# platform_smd2_o2.net
KiCad netlist of a schematic drawn in EAGLE
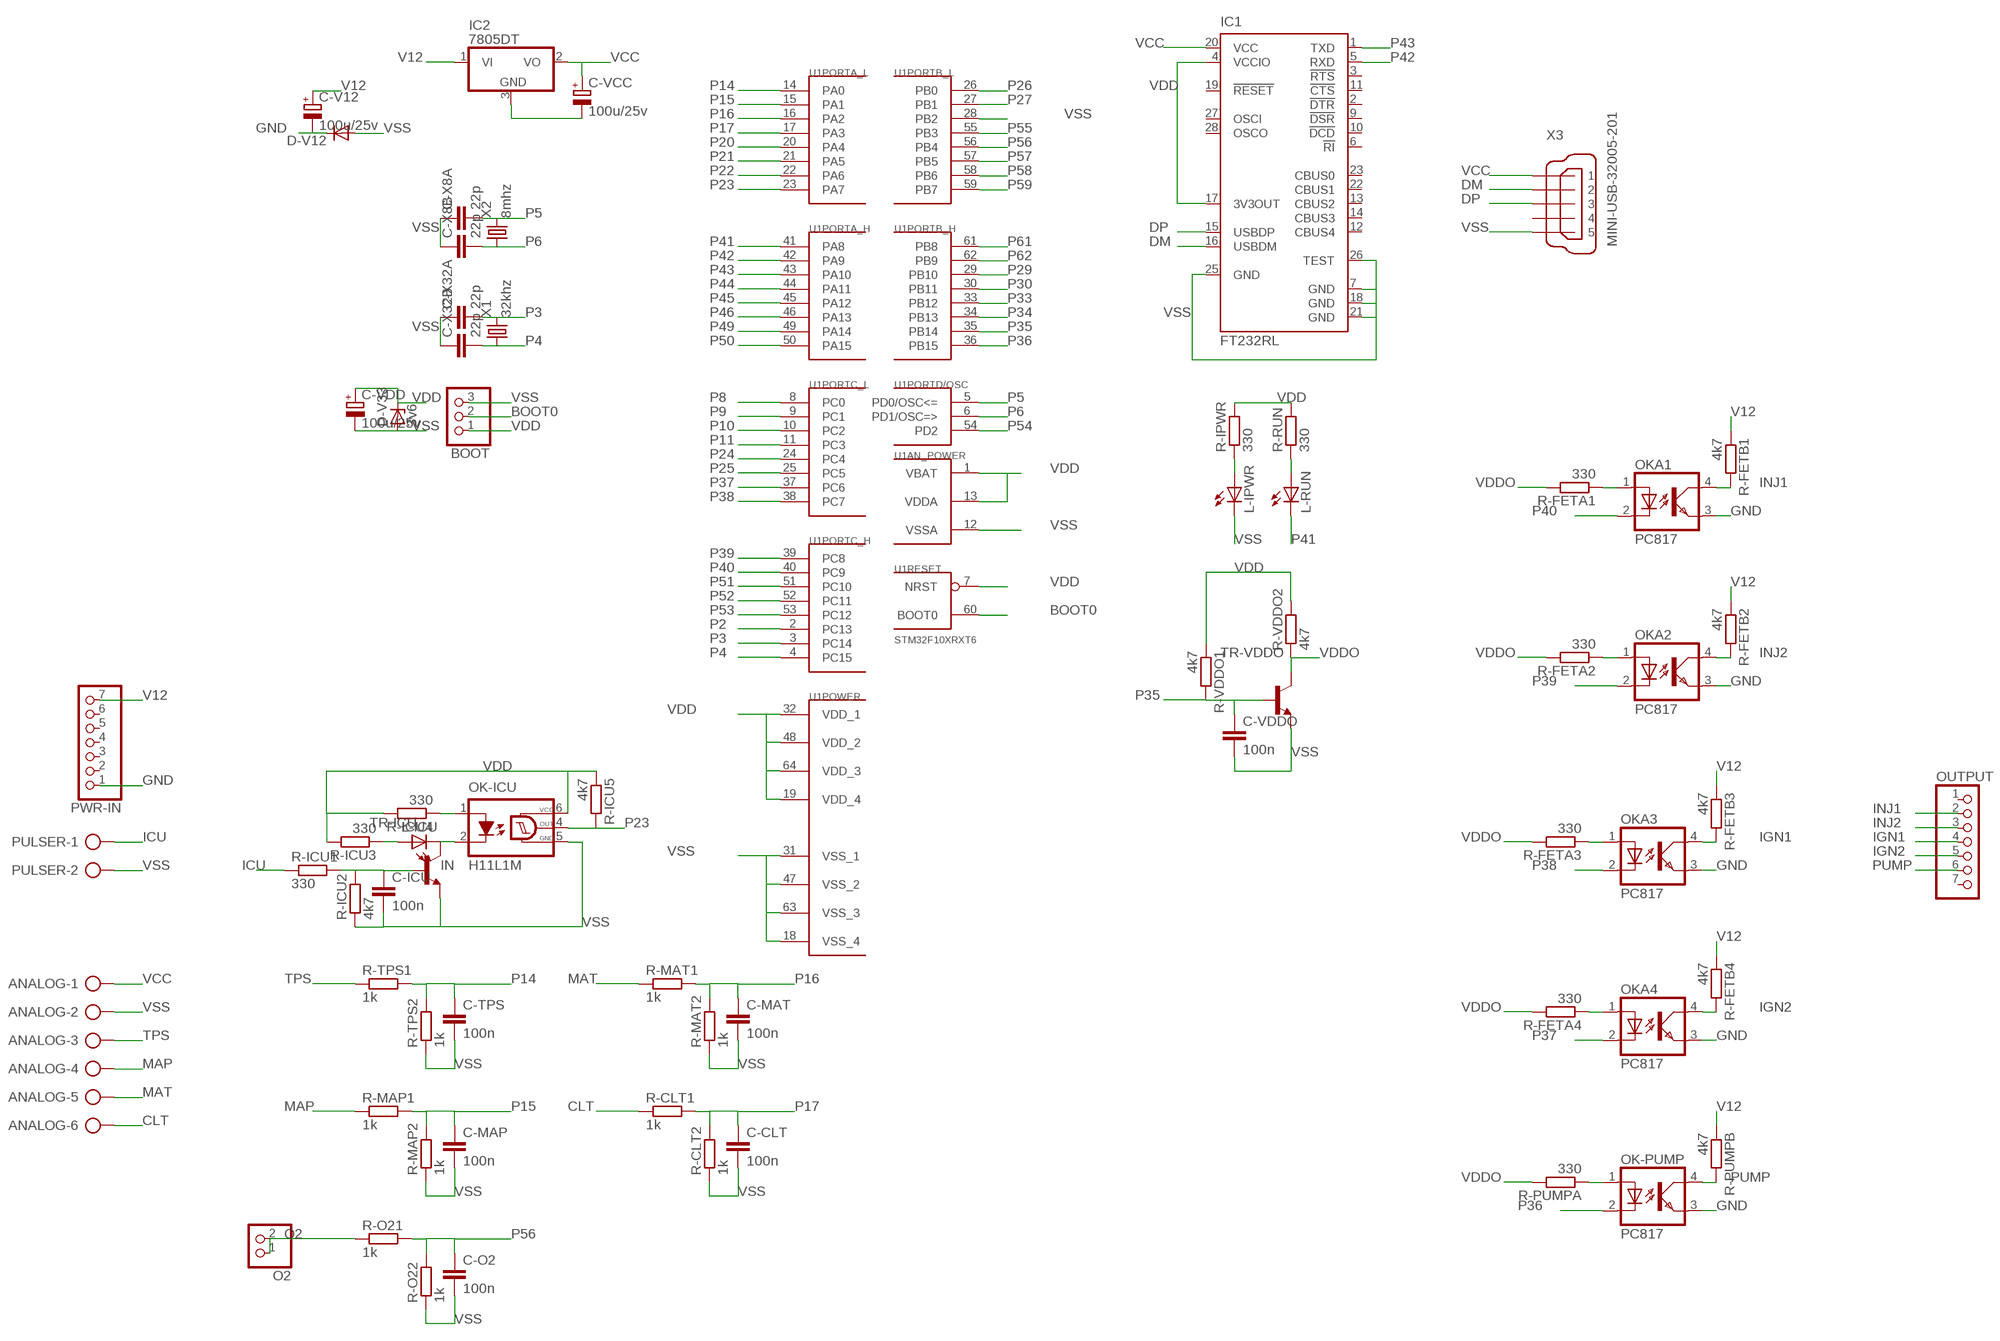
[diagram p0: schematic, sheet 1]

(export (version "E")
  (design (tool "Eeschema 10.0.6"))
  (components
    (comp (ref "ANALOG")
      (value "AK300/6")
      (footprint "eagle-import:AK300_6")
      (libsource (lib "eagle-import") (part "AK300/6"))
    )
    (comp (ref "BOOT")
      (value "PINHD-1X3")
      (footprint "eagle-import:1X03")
      (libsource (lib "eagle-import") (part "PINHD-1X3"))
    )
    (comp (ref "C-CLT")
      (value "100n")
      (footprint "eagle-import:C1206")
      (libsource (lib "eagle-import") (part "C-EUC1206"))
    )
    (comp (ref "C-ICU")
      (value "100n")
      (footprint "eagle-import:C1206")
      (libsource (lib "eagle-import") (part "C-EUC1206"))
    )
    (comp (ref "C-MAP")
      (value "100n")
      (footprint "eagle-import:C1206")
      (libsource (lib "eagle-import") (part "C-EUC1206"))
    )
    (comp (ref "C-MAT")
      (value "100n")
      (footprint "eagle-import:C1206")
      (libsource (lib "eagle-import") (part "C-EUC1206"))
    )
    (comp (ref "C-O2")
      (value "100n")
      (footprint "eagle-import:C1206")
      (libsource (lib "eagle-import") (part "C-EUC1206"))
    )
    (comp (ref "C-TPS")
      (value "100n")
      (footprint "eagle-import:C1206")
      (libsource (lib "eagle-import") (part "C-EUC1206"))
    )
    (comp (ref "C-V12")
      (value "100u/25v")
      (footprint "eagle-import:PANASONIC_D")
      (libsource (lib "eagle-import") (part "CPOL-EUD"))
    )
    (comp (ref "C-VCC")
      (value "100u/25v")
      (footprint "eagle-import:PANASONIC_D")
      (libsource (lib "eagle-import") (part "CPOL-EUD"))
    )
    (comp (ref "C-VDD")
      (value "100u/25v")
      (footprint "eagle-import:PANASONIC_D")
      (libsource (lib "eagle-import") (part "CPOL-EUD"))
    )
    (comp (ref "C-VDDO")
      (value "100n")
      (footprint "eagle-import:C1206")
      (libsource (lib "eagle-import") (part "C-EUC1206"))
    )
    (comp (ref "C-X8A")
      (value "22p")
      (footprint "eagle-import:C1206")
      (libsource (lib "eagle-import") (part "C-EUC1206"))
    )
    (comp (ref "C-X8B")
      (value "22p")
      (footprint "eagle-import:C1206")
      (libsource (lib "eagle-import") (part "C-EUC1206"))
    )
    (comp (ref "C-X32A")
      (value "22p")
      (footprint "eagle-import:C1206")
      (libsource (lib "eagle-import") (part "C-EUC1206"))
    )
    (comp (ref "C-X32B")
      (value "22p")
      (footprint "eagle-import:C1206")
      (libsource (lib "eagle-import") (part "C-EUC1206"))
    )
    (comp (ref "D-V12")
      (value "DIODE-SMB")
      (footprint "eagle-import:SMB")
      (libsource (lib "eagle-import") (part "DIODE-SMB"))
    )
    (comp (ref "D-V33")
      (value "3v6")
      (footprint "eagle-import:SMB")
      (libsource (lib "eagle-import") (part "ZENER-DIODESMB"))
    )
    (comp (ref "IC1")
      (value "FT232RL")
      (footprint "eagle-import:SSOP28")
      (libsource (lib "eagle-import") (part "FT232RL"))
    )
    (comp (ref "IC2")
      (value "7805DT")
      (footprint "eagle-import:TO252")
      (libsource (lib "eagle-import") (part "78DT05"))
    )
    (comp (ref "L-ICU")
      (value "LEDSMT1206")
      (footprint "eagle-import:1206")
      (libsource (lib "eagle-import") (part "LEDSMT1206"))
    )
    (comp (ref "L-IPWR")
      (value "LEDSMT1206")
      (footprint "eagle-import:1206")
      (libsource (lib "eagle-import") (part "LEDSMT1206"))
    )
    (comp (ref "L-RUN")
      (value "LEDSMT1206")
      (footprint "eagle-import:1206")
      (libsource (lib "eagle-import") (part "LEDSMT1206"))
    )
    (comp (ref "O2")
      (value "PINHD-1X2")
      (footprint "eagle-import:1X02")
      (libsource (lib "eagle-import") (part "PINHD-1X2"))
    )
    (comp (ref "OK-ICU")
      (value "H11L1M")
      (footprint "eagle-import:DIL06")
      (fields (field (name "MF") "FAIRCHILD SEMICONDUCTOR") (field (name "MPN") "H11L1-M"))
      (libsource (lib "eagle-import") (part "H11LM1"))
    )
    (comp (ref "OK-PUMP")
      (value "PC817")
      (footprint "eagle-import:DIL04")
      (fields (field (name "MPN") "PC817X4J000F"))
      (libsource (lib "eagle-import") (part "PC817"))
    )
    (comp (ref "OKA1")
      (value "PC817")
      (footprint "eagle-import:DIL04")
      (fields (field (name "MPN") "PC817X4J000F"))
      (libsource (lib "eagle-import") (part "PC817"))
    )
    (comp (ref "OKA2")
      (value "PC817")
      (footprint "eagle-import:DIL04")
      (fields (field (name "MPN") "PC817X4J000F"))
      (libsource (lib "eagle-import") (part "PC817"))
    )
    (comp (ref "OKA3")
      (value "PC817")
      (footprint "eagle-import:DIL04")
      (fields (field (name "MPN") "PC817X4J000F"))
      (libsource (lib "eagle-import") (part "PC817"))
    )
    (comp (ref "OKA4")
      (value "PC817")
      (footprint "eagle-import:DIL04")
      (fields (field (name "MPN") "PC817X4J000F"))
      (libsource (lib "eagle-import") (part "PC817"))
    )
    (comp (ref "OUTPUT")
      (value "PINHD-1X7")
      (footprint "eagle-import:1X07")
      (libsource (lib "eagle-import") (part "PINHD-1X7"))
    )
    (comp (ref "PULSER")
      (value "AK300/2")
      (footprint "eagle-import:AK300_2")
      (libsource (lib "eagle-import") (part "AK300/2"))
    )
    (comp (ref "PWR-IN")
      (value "PINHD-1X7")
      (footprint "eagle-import:1X07")
      (libsource (lib "eagle-import") (part "PINHD-1X7"))
    )
    (comp (ref "R-CLT1")
      (value "1k")
      (footprint "eagle-import:R1206")
      (libsource (lib "eagle-import") (part "R-EU_R1206"))
    )
    (comp (ref "R-CLT2")
      (value "1k")
      (footprint "eagle-import:R1206")
      (libsource (lib "eagle-import") (part "R-EU_R1206"))
    )
    (comp (ref "R-FETA1")
      (value "330")
      (footprint "eagle-import:R1206")
      (libsource (lib "eagle-import") (part "R-EU_R1206"))
    )
    (comp (ref "R-FETA2")
      (value "330")
      (footprint "eagle-import:R1206")
      (libsource (lib "eagle-import") (part "R-EU_R1206"))
    )
    (comp (ref "R-FETA3")
      (value "330")
      (footprint "eagle-import:R1206")
      (libsource (lib "eagle-import") (part "R-EU_R1206"))
    )
    (comp (ref "R-FETA4")
      (value "330")
      (footprint "eagle-import:R1206")
      (libsource (lib "eagle-import") (part "R-EU_R1206"))
    )
    (comp (ref "R-FETB1")
      (value "4k7")
      (footprint "eagle-import:R1206")
      (libsource (lib "eagle-import") (part "R-EU_R1206"))
    )
    (comp (ref "R-FETB2")
      (value "4k7")
      (footprint "eagle-import:R1206")
      (libsource (lib "eagle-import") (part "R-EU_R1206"))
    )
    (comp (ref "R-FETB3")
      (value "4k7")
      (footprint "eagle-import:R1206")
      (libsource (lib "eagle-import") (part "R-EU_R1206"))
    )
    (comp (ref "R-FETB4")
      (value "4k7")
      (footprint "eagle-import:R1206")
      (libsource (lib "eagle-import") (part "R-EU_R1206"))
    )
    (comp (ref "R-ICU1")
      (value "330")
      (footprint "eagle-import:R1206")
      (libsource (lib "eagle-import") (part "R-EU_R1206"))
    )
    (comp (ref "R-ICU2")
      (value "4k7")
      (footprint "eagle-import:R1206")
      (libsource (lib "eagle-import") (part "R-EU_R1206"))
    )
    (comp (ref "R-ICU3")
      (value "330")
      (footprint "eagle-import:R1206")
      (libsource (lib "eagle-import") (part "R-EU_R1206"))
    )
    (comp (ref "R-ICU4")
      (value "330")
      (footprint "eagle-import:R1206")
      (libsource (lib "eagle-import") (part "R-EU_R1206"))
    )
    (comp (ref "R-ICU5")
      (value "4k7")
      (footprint "eagle-import:R1206")
      (libsource (lib "eagle-import") (part "R-EU_R1206"))
    )
    (comp (ref "R-IPWR")
      (value "330")
      (footprint "eagle-import:R1206")
      (libsource (lib "eagle-import") (part "R-EU_R1206"))
    )
    (comp (ref "R-MAP1")
      (value "1k")
      (footprint "eagle-import:R1206")
      (libsource (lib "eagle-import") (part "R-EU_R1206"))
    )
    (comp (ref "R-MAP2")
      (value "1k")
      (footprint "eagle-import:R1206")
      (libsource (lib "eagle-import") (part "R-EU_R1206"))
    )
    (comp (ref "R-MAT1")
      (value "1k")
      (footprint "eagle-import:R1206")
      (libsource (lib "eagle-import") (part "R-EU_R1206"))
    )
    (comp (ref "R-MAT2")
      (value "1k")
      (footprint "eagle-import:R1206")
      (libsource (lib "eagle-import") (part "R-EU_R1206"))
    )
    (comp (ref "R-O21")
      (value "1k")
      (footprint "eagle-import:R1206")
      (libsource (lib "eagle-import") (part "R-EU_R1206"))
    )
    (comp (ref "R-O22")
      (value "1k")
      (footprint "eagle-import:R1206")
      (libsource (lib "eagle-import") (part "R-EU_R1206"))
    )
    (comp (ref "R-PUMPA")
      (value "330")
      (footprint "eagle-import:R1206")
      (libsource (lib "eagle-import") (part "R-EU_R1206"))
    )
    (comp (ref "R-PUMPB")
      (value "4k7")
      (footprint "eagle-import:R1206")
      (libsource (lib "eagle-import") (part "R-EU_R1206"))
    )
    (comp (ref "R-RUN")
      (value "330")
      (footprint "eagle-import:R1206")
      (libsource (lib "eagle-import") (part "R-EU_R1206"))
    )
    (comp (ref "R-TPS1")
      (value "1k")
      (footprint "eagle-import:R1206")
      (libsource (lib "eagle-import") (part "R-EU_R1206"))
    )
    (comp (ref "R-TPS2")
      (value "1k")
      (footprint "eagle-import:R1206")
      (libsource (lib "eagle-import") (part "R-EU_R1206"))
    )
    (comp (ref "R-VDDO1")
      (value "4k7")
      (footprint "eagle-import:M1206")
      (libsource (lib "eagle-import") (part "R-EU_M1206"))
    )
    (comp (ref "R-VDDO2")
      (value "4k7")
      (footprint "eagle-import:M1206")
      (libsource (lib "eagle-import") (part "R-EU_M1206"))
    )
    (comp (ref "TR-ICU")
      (value "MMBT3904LT1-NPN-SOT23-BEC")
      (footprint "eagle-import:SOT23-BEC")
      (libsource (lib "eagle-import") (part "-NPN-SOT23-BECMMBT3904LT1"))
    )
    (comp (ref "TR-VDDO")
      (value "MMBT3904LT1-NPN-SOT23-BEC")
      (footprint "eagle-import:SOT23-BEC")
      (libsource (lib "eagle-import") (part "-NPN-SOT23-BECMMBT3904LT1"))
    )
    (comp (ref "U1")
      (value "STM32F10XRXT6")
      (footprint "eagle-import:TQFP64")
      (libsource (lib "eagle-import") (part "STM32F10XRXT6"))
    )
    (comp (ref "X1")
      (value "32khz")
      (footprint "eagle-import:TC26V")
      (libsource (lib "eagle-import") (part "CRYSTALTC26V"))
    )
    (comp (ref "X2")
      (value "8mhz")
      (footprint "eagle-import:HC49U-V")
      (libsource (lib "eagle-import") (part "CRYSTALHC49U-V"))
    )
    (comp (ref "X3")
      (value "MINI-USB-32005-201")
      (footprint "eagle-import:32005-201")
      (libsource (lib "eagle-import") (part "MINI-USB-32005-201"))
    )
  )
  (nets
    (net (code "1") (name "/BOOT0") (class "Default")
      (node (ref "BOOT") (pin "2") (pinfunction "2_2") (pintype "passive"))
      (node (ref "U1") (pin "60") (pinfunction "BOOT0_60") (pintype "input"))
    )
    (net (code "2") (name "/CLT") (class "Default")
      (node (ref "ANALOG") (pin "6") (pinfunction "KL_6") (pintype "passive"))
      (node (ref "R-CLT1") (pin "1") (pinfunction "1_1") (pintype "passive"))
    )
    (net (code "3") (name "/DM") (class "Default")
      (node (ref "IC1") (pin "16") (pinfunction "USBDM_16") (pintype "bidirectional"))
      (node (ref "X3") (pin "2") (pinfunction "2_2") (pintype "passive"))
    )
    (net (code "4") (name "/DP") (class "Default")
      (node (ref "IC1") (pin "15") (pinfunction "USBDP_15") (pintype "bidirectional"))
      (node (ref "X3") (pin "3") (pinfunction "3_3") (pintype "passive"))
    )
    (net (code "5") (name "/GND") (class "Default")
      (node (ref "C-V12") (pin "-") (pinfunction "-_-") (pintype "passive"))
      (node (ref "D-V12") (pin "C") (pinfunction "C_C") (pintype "passive"))
      (node (ref "OK-PUMP") (pin "3") (pinfunction "EMIT_3") (pintype "passive"))
      (node (ref "OKA1") (pin "3") (pinfunction "EMIT_3") (pintype "passive"))
      (node (ref "OKA2") (pin "3") (pinfunction "EMIT_3") (pintype "passive"))
      (node (ref "OKA3") (pin "3") (pinfunction "EMIT_3") (pintype "passive"))
      (node (ref "OKA4") (pin "3") (pinfunction "EMIT_3") (pintype "passive"))
      (node (ref "PWR-IN") (pin "1") (pinfunction "1_1") (pintype "passive"))
    )
    (net (code "6") (name "/ICU") (class "Default")
      (node (ref "PULSER") (pin "1") (pinfunction "KL_1") (pintype "passive"))
      (node (ref "R-ICU1") (pin "1") (pinfunction "1_1") (pintype "passive"))
    )
    (net (code "7") (name "/IGN1") (class "Default")
      (node (ref "OKA3") (pin "4") (pinfunction "COL_4") (pintype "passive"))
      (node (ref "OUTPUT") (pin "4") (pinfunction "4_4") (pintype "passive"))
      (node (ref "R-FETB3") (pin "2") (pinfunction "2_2") (pintype "passive"))
    )
    (net (code "8") (name "/IGN2") (class "Default")
      (node (ref "OKA4") (pin "4") (pinfunction "COL_4") (pintype "passive"))
      (node (ref "OUTPUT") (pin "5") (pinfunction "5_5") (pintype "passive"))
      (node (ref "R-FETB4") (pin "2") (pinfunction "2_2") (pintype "passive"))
    )
    (net (code "9") (name "/IN") (class "Default")
      (node (ref "L-ICU") (pin "C") (pinfunction "C_C") (pintype "passive"))
      (node (ref "OK-ICU") (pin "2") (pinfunction "C_2") (pintype "passive"))
      (node (ref "TR-ICU") (pin "C") (pinfunction "C_C") (pintype "passive"))
    )
    (net (code "10") (name "/INJ1") (class "Default")
      (node (ref "OKA1") (pin "4") (pinfunction "COL_4") (pintype "passive"))
      (node (ref "OUTPUT") (pin "2") (pinfunction "2_2") (pintype "passive"))
      (node (ref "R-FETB1") (pin "2") (pinfunction "2_2") (pintype "passive"))
    )
    (net (code "11") (name "/INJ2") (class "Default")
      (node (ref "OKA2") (pin "4") (pinfunction "COL_4") (pintype "passive"))
      (node (ref "OUTPUT") (pin "3") (pinfunction "3_3") (pintype "passive"))
      (node (ref "R-FETB2") (pin "2") (pinfunction "2_2") (pintype "passive"))
    )
    (net (code "12") (name "/MAP") (class "Default")
      (node (ref "ANALOG") (pin "4") (pinfunction "KL_4") (pintype "passive"))
      (node (ref "R-MAP1") (pin "1") (pinfunction "1_1") (pintype "passive"))
    )
    (net (code "13") (name "/MAT") (class "Default")
      (node (ref "ANALOG") (pin "5") (pinfunction "KL_5") (pintype "passive"))
      (node (ref "R-MAT1") (pin "1") (pinfunction "1_1") (pintype "passive"))
    )
    (net (code "14") (name "/O2") (class "Default")
      (node (ref "O2") (pin "1") (pinfunction "1_1") (pintype "passive"))
      (node (ref "O2") (pin "2") (pinfunction "2_2") (pintype "passive"))
      (node (ref "R-O21") (pin "1") (pinfunction "1_1") (pintype "passive"))
    )
    (net (code "15") (name "/P2") (class "Default")
      (node (ref "U1") (pin "2") (pinfunction "PC13_2") (pintype "bidirectional"))
    )
    (net (code "16") (name "/P3") (class "Default")
      (node (ref "C-X32A") (pin "2") (pinfunction "2_2") (pintype "passive"))
      (node (ref "U1") (pin "3") (pinfunction "PC14_3") (pintype "bidirectional"))
      (node (ref "X1") (pin "2") (pinfunction "2_2") (pintype "passive"))
    )
    (net (code "17") (name "/P4") (class "Default")
      (node (ref "C-X32B") (pin "2") (pinfunction "2_2") (pintype "passive"))
      (node (ref "U1") (pin "4") (pinfunction "PC15_4") (pintype "bidirectional"))
      (node (ref "X1") (pin "1") (pinfunction "1_1") (pintype "passive"))
    )
    (net (code "18") (name "/P5") (class "Default")
      (node (ref "C-X8A") (pin "2") (pinfunction "2_2") (pintype "passive"))
      (node (ref "U1") (pin "5") (pinfunction "PD0/OSC<=_5") (pintype "bidirectional"))
      (node (ref "X2") (pin "2") (pinfunction "2_2") (pintype "passive"))
    )
    (net (code "19") (name "/P6") (class "Default")
      (node (ref "C-X8B") (pin "2") (pinfunction "2_2") (pintype "passive"))
      (node (ref "U1") (pin "6") (pinfunction "PD1/OSC=>_6") (pintype "bidirectional"))
      (node (ref "X2") (pin "1") (pinfunction "1_1") (pintype "passive"))
    )
    (net (code "20") (name "/P8") (class "Default")
      (node (ref "U1") (pin "8") (pinfunction "PC0_8") (pintype "bidirectional"))
    )
    (net (code "21") (name "/P9") (class "Default")
      (node (ref "U1") (pin "9") (pinfunction "PC1_9") (pintype "bidirectional"))
    )
    (net (code "22") (name "/P10") (class "Default")
      (node (ref "U1") (pin "10") (pinfunction "PC2_10") (pintype "bidirectional"))
    )
    (net (code "23") (name "/P11") (class "Default")
      (node (ref "U1") (pin "11") (pinfunction "PC3_11") (pintype "bidirectional"))
    )
    (net (code "24") (name "/P14") (class "Default")
      (node (ref "C-TPS") (pin "1") (pinfunction "1_1") (pintype "passive"))
      (node (ref "R-TPS1") (pin "2") (pinfunction "2_2") (pintype "passive"))
      (node (ref "R-TPS2") (pin "2") (pinfunction "2_2") (pintype "passive"))
      (node (ref "U1") (pin "14") (pinfunction "PA0_14") (pintype "bidirectional"))
    )
    (net (code "25") (name "/P15") (class "Default")
      (node (ref "C-MAP") (pin "1") (pinfunction "1_1") (pintype "passive"))
      (node (ref "R-MAP1") (pin "2") (pinfunction "2_2") (pintype "passive"))
      (node (ref "R-MAP2") (pin "2") (pinfunction "2_2") (pintype "passive"))
      (node (ref "U1") (pin "15") (pinfunction "PA1_15") (pintype "bidirectional"))
    )
    (net (code "26") (name "/P16") (class "Default")
      (node (ref "C-MAT") (pin "1") (pinfunction "1_1") (pintype "passive"))
      (node (ref "R-MAT1") (pin "2") (pinfunction "2_2") (pintype "passive"))
      (node (ref "R-MAT2") (pin "2") (pinfunction "2_2") (pintype "passive"))
      (node (ref "U1") (pin "16") (pinfunction "PA2_16") (pintype "bidirectional"))
    )
    (net (code "27") (name "/P17") (class "Default")
      (node (ref "C-CLT") (pin "1") (pinfunction "1_1") (pintype "passive"))
      (node (ref "R-CLT1") (pin "2") (pinfunction "2_2") (pintype "passive"))
      (node (ref "R-CLT2") (pin "2") (pinfunction "2_2") (pintype "passive"))
      (node (ref "U1") (pin "17") (pinfunction "PA3_17") (pintype "bidirectional"))
    )
    (net (code "28") (name "/P20") (class "Default")
      (node (ref "U1") (pin "20") (pinfunction "PA4_20") (pintype "bidirectional"))
    )
    (net (code "29") (name "/P21") (class "Default")
      (node (ref "U1") (pin "21") (pinfunction "PA5_21") (pintype "bidirectional"))
    )
    (net (code "30") (name "/P22") (class "Default")
      (node (ref "U1") (pin "22") (pinfunction "PA6_22") (pintype "bidirectional"))
    )
    (net (code "31") (name "/P23") (class "Default")
      (node (ref "OK-ICU") (pin "4") (pinfunction "OUT_4") (pintype "output"))
      (node (ref "R-ICU5") (pin "2") (pinfunction "2_2") (pintype "passive"))
      (node (ref "U1") (pin "23") (pinfunction "PA7_23") (pintype "bidirectional"))
    )
    (net (code "32") (name "/P24") (class "Default")
      (node (ref "U1") (pin "24") (pinfunction "PC4_24") (pintype "bidirectional"))
    )
    (net (code "33") (name "/P25") (class "Default")
      (node (ref "U1") (pin "25") (pinfunction "PC5_25") (pintype "bidirectional"))
    )
    (net (code "34") (name "/P26") (class "Default")
      (node (ref "U1") (pin "26") (pinfunction "PB0_26") (pintype "bidirectional"))
    )
    (net (code "35") (name "/P27") (class "Default")
      (node (ref "U1") (pin "27") (pinfunction "PB1_27") (pintype "bidirectional"))
    )
    (net (code "36") (name "/P29") (class "Default")
      (node (ref "U1") (pin "29") (pinfunction "PB10_29") (pintype "bidirectional"))
    )
    (net (code "37") (name "/P30") (class "Default")
      (node (ref "U1") (pin "30") (pinfunction "PB11_30") (pintype "bidirectional"))
    )
    (net (code "38") (name "/P33") (class "Default")
      (node (ref "U1") (pin "33") (pinfunction "PB12_33") (pintype "bidirectional"))
    )
    (net (code "39") (name "/P34") (class "Default")
      (node (ref "U1") (pin "34") (pinfunction "PB13_34") (pintype "bidirectional"))
    )
    (net (code "40") (name "/P35") (class "Default")
      (node (ref "C-VDDO") (pin "1") (pinfunction "1_1") (pintype "passive"))
      (node (ref "R-VDDO1") (pin "2") (pinfunction "2_2") (pintype "passive"))
      (node (ref "TR-VDDO") (pin "B") (pinfunction "B_B") (pintype "passive"))
      (node (ref "U1") (pin "35") (pinfunction "PB14_35") (pintype "bidirectional"))
    )
    (net (code "41") (name "/P36") (class "Default")
      (node (ref "OK-PUMP") (pin "2") (pinfunction "C_2") (pintype "passive"))
      (node (ref "U1") (pin "36") (pinfunction "PB15_36") (pintype "bidirectional"))
    )
    (net (code "42") (name "/P37") (class "Default")
      (node (ref "OKA4") (pin "2") (pinfunction "C_2") (pintype "passive"))
      (node (ref "U1") (pin "37") (pinfunction "PC6_37") (pintype "bidirectional"))
    )
    (net (code "43") (name "/P38") (class "Default")
      (node (ref "OKA3") (pin "2") (pinfunction "C_2") (pintype "passive"))
      (node (ref "U1") (pin "38") (pinfunction "PC7_38") (pintype "bidirectional"))
    )
    (net (code "44") (name "/P39") (class "Default")
      (node (ref "OKA2") (pin "2") (pinfunction "C_2") (pintype "passive"))
      (node (ref "U1") (pin "39") (pinfunction "PC8_39") (pintype "bidirectional"))
    )
    (net (code "45") (name "/P40") (class "Default")
      (node (ref "OKA1") (pin "2") (pinfunction "C_2") (pintype "passive"))
      (node (ref "U1") (pin "40") (pinfunction "PC9_40") (pintype "bidirectional"))
    )
    (net (code "46") (name "/P41") (class "Default")
      (node (ref "L-RUN") (pin "C") (pinfunction "C_C") (pintype "passive"))
      (node (ref "U1") (pin "41") (pinfunction "PA8_41") (pintype "bidirectional"))
    )
    (net (code "47") (name "/P42") (class "Default")
      (node (ref "IC1") (pin "5") (pinfunction "RXD_5") (pintype "input"))
      (node (ref "U1") (pin "42") (pinfunction "PA9_42") (pintype "bidirectional"))
    )
    (net (code "48") (name "/P43") (class "Default")
      (node (ref "IC1") (pin "1") (pinfunction "TXD_1") (pintype "output"))
      (node (ref "U1") (pin "43") (pinfunction "PA10_43") (pintype "bidirectional"))
    )
    (net (code "49") (name "/P44") (class "Default")
      (node (ref "U1") (pin "44") (pinfunction "PA11_44") (pintype "bidirectional"))
    )
    (net (code "50") (name "/P45") (class "Default")
      (node (ref "U1") (pin "45") (pinfunction "PA12_45") (pintype "bidirectional"))
    )
    (net (code "51") (name "/P46") (class "Default")
      (node (ref "U1") (pin "46") (pinfunction "PA13_46") (pintype "bidirectional"))
    )
    (net (code "52") (name "/P49") (class "Default")
      (node (ref "U1") (pin "49") (pinfunction "PA14_49") (pintype "bidirectional"))
    )
    (net (code "53") (name "/P50") (class "Default")
      (node (ref "U1") (pin "50") (pinfunction "PA15_50") (pintype "bidirectional"))
    )
    (net (code "54") (name "/P51") (class "Default")
      (node (ref "U1") (pin "51") (pinfunction "PC10_51") (pintype "bidirectional"))
    )
    (net (code "55") (name "/P52") (class "Default")
      (node (ref "U1") (pin "52") (pinfunction "PC11_52") (pintype "bidirectional"))
    )
    (net (code "56") (name "/P53") (class "Default")
      (node (ref "U1") (pin "53") (pinfunction "PC12_53") (pintype "bidirectional"))
    )
    (net (code "57") (name "/P54") (class "Default")
      (node (ref "U1") (pin "54") (pinfunction "PD2_54") (pintype "bidirectional"))
    )
    (net (code "58") (name "/P55") (class "Default")
      (node (ref "U1") (pin "55") (pinfunction "PB3_55") (pintype "bidirectional"))
    )
    (net (code "59") (name "/P56") (class "Default")
      (node (ref "C-O2") (pin "1") (pinfunction "1_1") (pintype "passive"))
      (node (ref "R-O21") (pin "2") (pinfunction "2_2") (pintype "passive"))
      (node (ref "R-O22") (pin "2") (pinfunction "2_2") (pintype "passive"))
      (node (ref "U1") (pin "56") (pinfunction "PB4_56") (pintype "bidirectional"))
    )
    (net (code "60") (name "/P57") (class "Default")
      (node (ref "U1") (pin "57") (pinfunction "PB5_57") (pintype "bidirectional"))
    )
    (net (code "61") (name "/P58") (class "Default")
      (node (ref "U1") (pin "58") (pinfunction "PB6_58") (pintype "bidirectional"))
    )
    (net (code "62") (name "/P59") (class "Default")
      (node (ref "U1") (pin "59") (pinfunction "PB7_59") (pintype "bidirectional"))
    )
    (net (code "63") (name "/P61") (class "Default")
      (node (ref "U1") (pin "61") (pinfunction "PB8_61") (pintype "bidirectional"))
    )
    (net (code "64") (name "/P62") (class "Default")
      (node (ref "U1") (pin "62") (pinfunction "PB9_62") (pintype "bidirectional"))
    )
    (net (code "65") (name "/PUMP") (class "Default")
      (node (ref "OK-PUMP") (pin "4") (pinfunction "COL_4") (pintype "passive"))
      (node (ref "OUTPUT") (pin "6") (pinfunction "6_6") (pintype "passive"))
      (node (ref "R-PUMPB") (pin "2") (pinfunction "2_2") (pintype "passive"))
    )
    (net (code "66") (name "/TPS") (class "Default")
      (node (ref "ANALOG") (pin "3") (pinfunction "KL_3") (pintype "passive"))
      (node (ref "R-TPS1") (pin "1") (pinfunction "1_1") (pintype "passive"))
    )
    (net (code "67") (name "/V12") (class "Default")
      (node (ref "C-V12") (pin "+") (pinfunction "+_+") (pintype "passive"))
      (node (ref "IC2") (pin "1") (pinfunction "VI_1") (pintype "input"))
      (node (ref "PWR-IN") (pin "7") (pinfunction "7_7") (pintype "passive"))
      (node (ref "R-FETB1") (pin "1") (pinfunction "1_1") (pintype "passive"))
      (node (ref "R-FETB2") (pin "1") (pinfunction "1_1") (pintype "passive"))
      (node (ref "R-FETB3") (pin "1") (pinfunction "1_1") (pintype "passive"))
      (node (ref "R-FETB4") (pin "1") (pinfunction "1_1") (pintype "passive"))
      (node (ref "R-PUMPB") (pin "1") (pinfunction "1_1") (pintype "passive"))
    )
    (net (code "68") (name "/VCC") (class "Default")
      (node (ref "ANALOG") (pin "1") (pinfunction "KL_1") (pintype "passive"))
      (node (ref "C-VCC") (pin "+") (pinfunction "+_+") (pintype "passive"))
      (node (ref "IC1") (pin "20") (pinfunction "VCC_20") (pintype "power_in"))
      (node (ref "IC2") (pin "2") (pinfunction "VO_2") (pintype "passive"))
      (node (ref "X3") (pin "1") (pinfunction "1_1") (pintype "passive"))
    )
    (net (code "69") (name "/VDD") (class "Default")
      (node (ref "BOOT") (pin "1") (pinfunction "1_1") (pintype "passive"))
      (node (ref "C-VDD") (pin "+") (pinfunction "+_+") (pintype "passive"))
      (node (ref "D-V33") (pin "C") (pinfunction "C_C") (pintype "passive"))
      (node (ref "IC1") (pin "17") (pinfunction "3V3OUT_17") (pintype "output"))
      (node (ref "IC1") (pin "4") (pinfunction "VCCIO_4") (pintype "power_in"))
      (node (ref "OK-ICU") (pin "6") (pinfunction "VCC_6") (pintype "power_in"))
      (node (ref "R-ICU3") (pin "2") (pinfunction "2_2") (pintype "passive"))
      (node (ref "R-ICU4") (pin "2") (pinfunction "2_2") (pintype "passive"))
      (node (ref "R-ICU5") (pin "1") (pinfunction "1_1") (pintype "passive"))
      (node (ref "R-IPWR") (pin "2") (pinfunction "2_2") (pintype "passive"))
      (node (ref "R-RUN") (pin "2") (pinfunction "2_2") (pintype "passive"))
      (node (ref "R-VDDO1") (pin "1") (pinfunction "1_1") (pintype "passive"))
      (node (ref "R-VDDO2") (pin "2") (pinfunction "2_2") (pintype "passive"))
      (node (ref "U1") (pin "1") (pinfunction "VBAT_1") (pintype "power_in"))
      (node (ref "U1") (pin "13") (pinfunction "VDDA_13") (pintype "power_in"))
      (node (ref "U1") (pin "19") (pinfunction "VDD_4_19") (pintype "power_in"))
      (node (ref "U1") (pin "32") (pinfunction "VDD_1_32") (pintype "power_in"))
      (node (ref "U1") (pin "48") (pinfunction "VDD_2_48") (pintype "power_in"))
      (node (ref "U1") (pin "64") (pinfunction "VDD_3_64") (pintype "power_in"))
      (node (ref "U1") (pin "7") (pinfunction "NRST_7") (pintype "input"))
    )
    (net (code "70") (name "/VDDO") (class "Default")
      (node (ref "R-FETA1") (pin "2") (pinfunction "2_2") (pintype "passive"))
      (node (ref "R-FETA2") (pin "2") (pinfunction "2_2") (pintype "passive"))
      (node (ref "R-FETA3") (pin "2") (pinfunction "2_2") (pintype "passive"))
      (node (ref "R-FETA4") (pin "2") (pinfunction "2_2") (pintype "passive"))
      (node (ref "R-PUMPA") (pin "2") (pinfunction "2_2") (pintype "passive"))
      (node (ref "R-VDDO2") (pin "1") (pinfunction "1_1") (pintype "passive"))
      (node (ref "TR-VDDO") (pin "C") (pinfunction "C_C") (pintype "passive"))
    )
    (net (code "71") (name "/VSS") (class "Default")
      (node (ref "ANALOG") (pin "2") (pinfunction "KL_2") (pintype "passive"))
      (node (ref "BOOT") (pin "3") (pinfunction "3_3") (pintype "passive"))
      (node (ref "C-CLT") (pin "2") (pinfunction "2_2") (pintype "passive"))
      (node (ref "C-ICU") (pin "2") (pinfunction "2_2") (pintype "passive"))
      (node (ref "C-MAP") (pin "2") (pinfunction "2_2") (pintype "passive"))
      (node (ref "C-MAT") (pin "2") (pinfunction "2_2") (pintype "passive"))
      (node (ref "C-O2") (pin "2") (pinfunction "2_2") (pintype "passive"))
      (node (ref "C-TPS") (pin "2") (pinfunction "2_2") (pintype "passive"))
      (node (ref "C-VCC") (pin "-") (pinfunction "-_-") (pintype "passive"))
      (node (ref "C-VDD") (pin "-") (pinfunction "-_-") (pintype "passive"))
      (node (ref "C-VDDO") (pin "2") (pinfunction "2_2") (pintype "passive"))
      (node (ref "C-X32A") (pin "1") (pinfunction "1_1") (pintype "passive"))
      (node (ref "C-X32B") (pin "1") (pinfunction "1_1") (pintype "passive"))
      (node (ref "C-X8A") (pin "1") (pinfunction "1_1") (pintype "passive"))
      (node (ref "C-X8B") (pin "1") (pinfunction "1_1") (pintype "passive"))
      (node (ref "D-V12") (pin "A") (pinfunction "A_A") (pintype "passive"))
      (node (ref "D-V33") (pin "A") (pinfunction "A_A") (pintype "passive"))
      (node (ref "IC1") (pin "18") (pinfunction "GND_18") (pintype "power_in"))
      (node (ref "IC1") (pin "21") (pinfunction "GND_21") (pintype "power_in"))
      (node (ref "IC1") (pin "25") (pinfunction "GND_25") (pintype "power_in"))
      (node (ref "IC1") (pin "26") (pinfunction "TEST_26") (pintype "input"))
      (node (ref "IC1") (pin "7") (pinfunction "GND_7") (pintype "power_in"))
      (node (ref "IC2") (pin "3") (pinfunction "GND_3") (pintype "passive"))
      (node (ref "L-IPWR") (pin "C") (pinfunction "C_C") (pintype "passive"))
      (node (ref "OK-ICU") (pin "5") (pinfunction "GND_5") (pintype "power_in"))
      (node (ref "PULSER") (pin "2") (pinfunction "KL_2") (pintype "passive"))
      (node (ref "R-CLT2") (pin "1") (pinfunction "1_1") (pintype "passive"))
      (node (ref "R-ICU2") (pin "1") (pinfunction "1_1") (pintype "passive"))
      (node (ref "R-MAP2") (pin "1") (pinfunction "1_1") (pintype "passive"))
      (node (ref "R-MAT2") (pin "1") (pinfunction "1_1") (pintype "passive"))
      (node (ref "R-O22") (pin "1") (pinfunction "1_1") (pintype "passive"))
      (node (ref "R-TPS2") (pin "1") (pinfunction "1_1") (pintype "passive"))
      (node (ref "TR-ICU") (pin "E") (pinfunction "E_E") (pintype "passive"))
      (node (ref "TR-VDDO") (pin "E") (pinfunction "E_E") (pintype "passive"))
      (node (ref "U1") (pin "12") (pinfunction "VSSA_12") (pintype "power_in"))
      (node (ref "U1") (pin "18") (pinfunction "VSS_4_18") (pintype "power_in"))
      (node (ref "U1") (pin "28") (pinfunction "PB2_28") (pintype "bidirectional"))
      (node (ref "U1") (pin "31") (pinfunction "VSS_1_31") (pintype "power_in"))
      (node (ref "U1") (pin "47") (pinfunction "VSS_2_47") (pintype "power_in"))
      (node (ref "U1") (pin "63") (pinfunction "VSS_3_63") (pintype "power_in"))
      (node (ref "X3") (pin "5") (pinfunction "5_5") (pintype "passive"))
    )
    (net (code "72") (name "Net-(C-ICU-Pad1)") (class "Default")
      (node (ref "C-ICU") (pin "1") (pinfunction "1_1") (pintype "passive"))
      (node (ref "R-ICU1") (pin "2") (pinfunction "2_2") (pintype "passive"))
      (node (ref "R-ICU2") (pin "2") (pinfunction "2_2") (pintype "passive"))
      (node (ref "TR-ICU") (pin "B") (pinfunction "B_B") (pintype "passive"))
    )
    (net (code "73") (name "Net-(L-ICU-PadA)") (class "Default")
      (node (ref "L-ICU") (pin "A") (pinfunction "A_A") (pintype "passive"))
      (node (ref "R-ICU3") (pin "1") (pinfunction "1_1") (pintype "passive"))
    )
    (net (code "74") (name "Net-(L-IPWR-PadA)") (class "Default")
      (node (ref "L-IPWR") (pin "A") (pinfunction "A_A") (pintype "passive"))
      (node (ref "R-IPWR") (pin "1") (pinfunction "1_1") (pintype "passive"))
    )
    (net (code "75") (name "Net-(L-RUN-PadA)") (class "Default")
      (node (ref "L-RUN") (pin "A") (pinfunction "A_A") (pintype "passive"))
      (node (ref "R-RUN") (pin "1") (pinfunction "1_1") (pintype "passive"))
    )
    (net (code "76") (name "Net-(OK-ICU-A)") (class "Default")
      (node (ref "OK-ICU") (pin "1") (pinfunction "A_1") (pintype "passive"))
      (node (ref "R-ICU4") (pin "1") (pinfunction "1_1") (pintype "passive"))
    )
    (net (code "77") (name "Net-(OK-PUMP-A)") (class "Default")
      (node (ref "OK-PUMP") (pin "1") (pinfunction "A_1") (pintype "passive"))
      (node (ref "R-PUMPA") (pin "1") (pinfunction "1_1") (pintype "passive"))
    )
    (net (code "78") (name "Net-(OKA1-A)") (class "Default")
      (node (ref "OKA1") (pin "1") (pinfunction "A_1") (pintype "passive"))
      (node (ref "R-FETA1") (pin "1") (pinfunction "1_1") (pintype "passive"))
    )
    (net (code "79") (name "Net-(OKA2-A)") (class "Default")
      (node (ref "OKA2") (pin "1") (pinfunction "A_1") (pintype "passive"))
      (node (ref "R-FETA2") (pin "1") (pinfunction "1_1") (pintype "passive"))
    )
    (net (code "80") (name "Net-(OKA3-A)") (class "Default")
      (node (ref "OKA3") (pin "1") (pinfunction "A_1") (pintype "passive"))
      (node (ref "R-FETA3") (pin "1") (pinfunction "1_1") (pintype "passive"))
    )
    (net (code "81") (name "Net-(OKA4-A)") (class "Default")
      (node (ref "OKA4") (pin "1") (pinfunction "A_1") (pintype "passive"))
      (node (ref "R-FETA4") (pin "1") (pinfunction "1_1") (pintype "passive"))
    )
    (net (code "82") (name "unconnected-(IC1-CBUS0-Pad23)") (class "Default")
      (node (ref "IC1") (pin "23") (pinfunction "CBUS0_23") (pintype "bidirectional"))
    )
    (net (code "83") (name "unconnected-(IC1-CBUS1-Pad22)") (class "Default")
      (node (ref "IC1") (pin "22") (pinfunction "CBUS1_22") (pintype "bidirectional"))
    )
    (net (code "84") (name "unconnected-(IC1-CBUS2-Pad13)") (class "Default")
      (node (ref "IC1") (pin "13") (pinfunction "CBUS2_13") (pintype "bidirectional"))
    )
    (net (code "85") (name "unconnected-(IC1-CBUS3-Pad14)") (class "Default")
      (node (ref "IC1") (pin "14") (pinfunction "CBUS3_14") (pintype "bidirectional"))
    )
    (net (code "86") (name "unconnected-(IC1-CBUS4-Pad12)") (class "Default")
      (node (ref "IC1") (pin "12") (pinfunction "CBUS4_12") (pintype "bidirectional"))
    )
    (net (code "87") (name "unconnected-(IC1-OSCI-Pad27)") (class "Default")
      (node (ref "IC1") (pin "27") (pinfunction "OSCI_27") (pintype "input"))
    )
    (net (code "88") (name "unconnected-(IC1-OSCO-Pad28)") (class "Default")
      (node (ref "IC1") (pin "28") (pinfunction "OSCO_28") (pintype "output"))
    )
    (net (code "89") (name "unconnected-(IC1-~{CTS}-Pad11)") (class "Default")
      (node (ref "IC1") (pin "11") (pinfunction "~{CTS}_11") (pintype "input"))
    )
    (net (code "90") (name "unconnected-(IC1-~{DCD}-Pad10)") (class "Default")
      (node (ref "IC1") (pin "10") (pinfunction "~{DCD}_10") (pintype "input"))
    )
    (net (code "91") (name "unconnected-(IC1-~{DSR}-Pad9)") (class "Default")
      (node (ref "IC1") (pin "9") (pinfunction "~{DSR}_9") (pintype "input"))
    )
    (net (code "92") (name "unconnected-(IC1-~{DTR}-Pad2)") (class "Default")
      (node (ref "IC1") (pin "2") (pinfunction "~{DTR}_2") (pintype "output"))
    )
    (net (code "93") (name "unconnected-(IC1-~{RESET}-Pad19)") (class "Default")
      (node (ref "IC1") (pin "19") (pinfunction "~{RESET}_19") (pintype "input"))
    )
    (net (code "94") (name "unconnected-(IC1-~{RI}-Pad6)") (class "Default")
      (node (ref "IC1") (pin "6") (pinfunction "~{RI}_6") (pintype "input"))
    )
    (net (code "95") (name "unconnected-(IC1-~{RTS}-Pad3)") (class "Default")
      (node (ref "IC1") (pin "3") (pinfunction "~{RTS}_3") (pintype "output"))
    )
    (net (code "96") (name "unconnected-(OUTPUT-Pad1)") (class "Default")
      (node (ref "OUTPUT") (pin "1") (pinfunction "1_1") (pintype "passive"))
    )
    (net (code "97") (name "unconnected-(OUTPUT-Pad7)") (class "Default")
      (node (ref "OUTPUT") (pin "7") (pinfunction "7_7") (pintype "passive"))
    )
    (net (code "98") (name "unconnected-(PWR-IN-Pad2)") (class "Default")
      (node (ref "PWR-IN") (pin "2") (pinfunction "2_2") (pintype "passive"))
    )
    (net (code "99") (name "unconnected-(PWR-IN-Pad3)") (class "Default")
      (node (ref "PWR-IN") (pin "3") (pinfunction "3_3") (pintype "passive"))
    )
    (net (code "100") (name "unconnected-(PWR-IN-Pad4)") (class "Default")
      (node (ref "PWR-IN") (pin "4") (pinfunction "4_4") (pintype "passive"))
    )
    (net (code "101") (name "unconnected-(PWR-IN-Pad5)") (class "Default")
      (node (ref "PWR-IN") (pin "5") (pinfunction "5_5") (pintype "passive"))
    )
    (net (code "102") (name "unconnected-(PWR-IN-Pad6)") (class "Default")
      (node (ref "PWR-IN") (pin "6") (pinfunction "6_6") (pintype "passive"))
    )
    (net (code "103") (name "unconnected-(X3-Pad4)") (class "Default")
      (node (ref "X3") (pin "4") (pinfunction "4_4") (pintype "passive"))
    )
  )
)
